# Altium_STM32_Schematic_SchDoc.net
KiCad netlist of a schematic drawn in Altium Designer
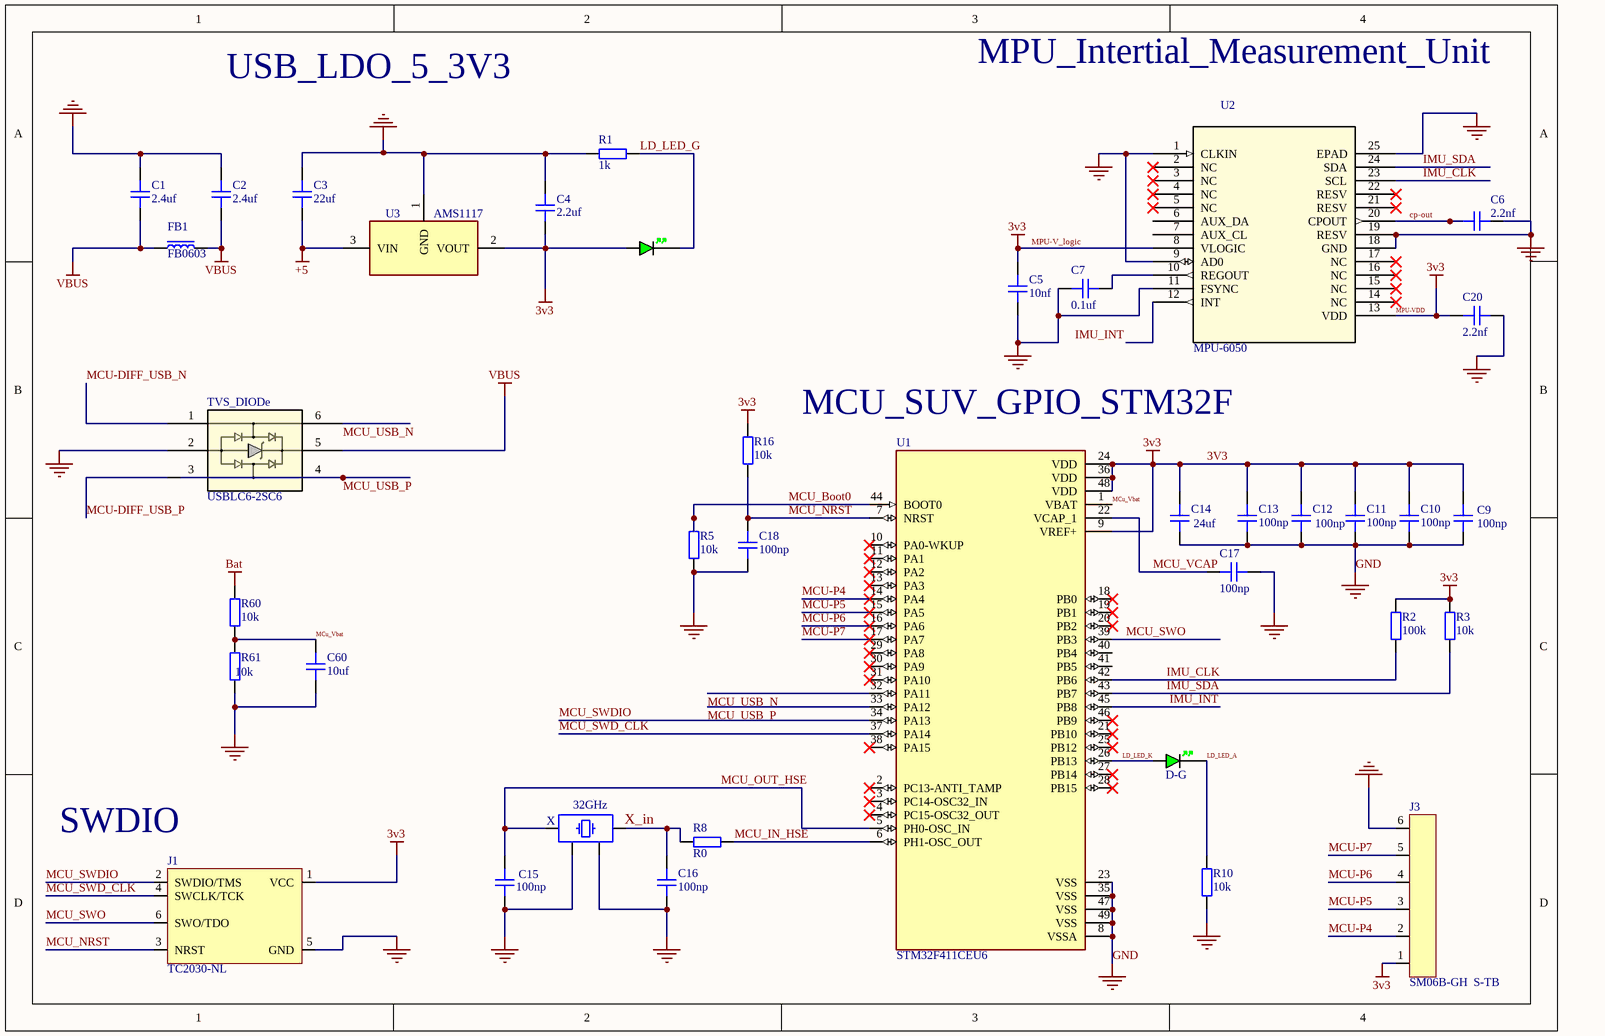
[diagram p0: Altium_STM32_Schematic_SchDoc.SchDoc]

(export (version "E")
  (design (tool "Eeschema 10.0.6"))
  (components
    (comp (ref "C1")
      (value "2.4uf")
      (footprint "CAP_0603")
      (description "Capacitor SMD 0603")
      (libsource (lib "Schematic-Lib-PhilsLab") (part "CAP_0603"))
    )
    (comp (ref "C2")
      (value "2.4uf")
      (footprint "CAP_0603")
      (description "Capacitor SMD 0603")
      (libsource (lib "Schematic-Lib-PhilsLab") (part "CAP_0603"))
    )
    (comp (ref "C3")
      (value "22uf")
      (footprint "CAP_0805")
      (description "Capacitor SMD 0805")
      (libsource (lib "Schematic-Lib-PhilsLab") (part "CAP_0805"))
    )
    (comp (ref "C4")
      (value "2.2uf")
      (footprint "CAP_0805")
      (description "Capacitor SMD 0805")
      (libsource (lib "Schematic-Lib-PhilsLab") (part "CAP_0805"))
    )
    (comp (ref "C5")
      (value "10nf")
      (footprint "CAP_0603")
      (description "Capacitor SMD 0603")
      (libsource (lib "Schematic-Lib-PhilsLab") (part "CAP_0603"))
    )
    (comp (ref "C6")
      (value "2.2nf")
      (footprint "CAP_0603")
      (description "Capacitor SMD 0603")
      (libsource (lib "Schematic-Lib-PhilsLab") (part "CAP_0603"))
    )
    (comp (ref "C7")
      (value "0.1uf")
      (footprint "CAP_0603")
      (description "Capacitor SMD 0603")
      (libsource (lib "Schematic-Lib-PhilsLab") (part "CAP_0603"))
    )
    (comp (ref "C9")
      (value "100np")
      (footprint "CAP_0402")
      (description "Capacitor SMD 0402")
      (libsource (lib "Schematic-Lib-PhilsLab") (part "CAP_0402"))
    )
    (comp (ref "C10")
      (value "100np")
      (footprint "CAP_0402")
      (description "Capacitor SMD 0402")
      (libsource (lib "Schematic-Lib-PhilsLab") (part "CAP_0402"))
    )
    (comp (ref "C11")
      (value "100np")
      (footprint "CAP_0402")
      (description "Capacitor SMD 0402")
      (libsource (lib "Schematic-Lib-PhilsLab") (part "CAP_0402"))
    )
    (comp (ref "C12")
      (value "100np")
      (footprint "CAP_0402")
      (description "Capacitor SMD 0402")
      (libsource (lib "Schematic-Lib-PhilsLab") (part "CAP_0402"))
    )
    (comp (ref "C13")
      (value "100np")
      (footprint "CAP_0402")
      (description "Capacitor SMD 0402")
      (libsource (lib "Schematic-Lib-PhilsLab") (part "CAP_0402"))
    )
    (comp (ref "C14")
      (value "24uf")
      (footprint "CAP_0603")
      (description "Capacitor SMD 0603")
      (libsource (lib "Schematic-Lib-PhilsLab") (part "CAP_0603"))
    )
    (comp (ref "C15")
      (value "100np")
      (footprint "CAP_0402")
      (description "Capacitor SMD 0402")
      (libsource (lib "Schematic-Lib-PhilsLab") (part "CAP_0402"))
    )
    (comp (ref "C16")
      (value "100np")
      (footprint "CAP_0402")
      (description "Capacitor SMD 0402")
      (libsource (lib "Schematic-Lib-PhilsLab") (part "CAP_0402"))
    )
    (comp (ref "C17")
      (value "100np")
      (footprint "CAP_0402")
      (description "Capacitor SMD 0402")
      (libsource (lib "Schematic-Lib-PhilsLab") (part "CAP_0402"))
    )
    (comp (ref "C18")
      (value "100np")
      (footprint "CAP_0402")
      (description "Capacitor SMD 0402")
      (libsource (lib "Schematic-Lib-PhilsLab") (part "CAP_0402"))
    )
    (comp (ref "C20")
      (value "2.2nf")
      (footprint "CAP_0603")
      (description "Capacitor SMD 0603")
      (libsource (lib "Schematic-Lib-PhilsLab") (part "CAP_0603"))
    )
    (comp (ref "C60")
      (value "10uf")
      (footprint "CAP_0402")
      (description "Capacitor SMD 0402")
      (libsource (lib "Schematic-Lib-PhilsLab") (part "CAP_0402"))
    )
    (comp (ref "D")
      (value "GREEN")
      (footprint "LED_0402_GREEN")
      (description "LED 0402 GREEN SMD")
      (libsource (lib "Schematic-Lib-PhilsLab") (part "LED_0402_GREEN"))
    )
    (comp (ref "D-G")
      (value "GREEN")
      (footprint "LED_0402_GREEN")
      (description "LED 0402 GREEN SMD")
      (libsource (lib "Schematic-Lib-PhilsLab") (part "LED_0402_GREEN"))
    )
    (comp (ref "FB1")
      (value "FB0603")
      (footprint "FB_0603")
      (description "Ferrite Bead SMD 0603")
      (libsource (lib "Schematic-Lib-PhilsLab") (part "FB_0603"))
    )
    (comp (ref "J1")
      (value "TC2030-NL")
      (footprint "TC2030-NL-FP")
      (description "Tag-Connect No-Solder SWD Debug Connector (No Legs) DO NOT PLACE")
      (fields
        (field (name "MANUFACTURER") "Tag-Connect")
        (field (name "MANUFACTURER PART NUMBER") "TC2030-NL-FP")
      )
      (libsource (lib "Schematic-Lib-PhilsLab") (part "TC2030-NL"))
    )
    (comp (ref "J3")
      (value "SM06B-GH  S-TB")
      (footprint "SM06B-GHS-TB")
      (description "Header Connector 6 Position 1.25MM Pitch SMD Horizontal JST GH")
      (fields (field (name "MANUFACTURER") "JST") (field (name "MANUFACTURER PART NUMBER") "SM06B-GHS-TB"))
      (libsource (lib "Schematic-Lib-PhilsLab") (part "SM06B-GHS-TB"))
    )
    (comp (ref "R1")
      (value "1k")
      (footprint "RES_0402")
      (description "Resistor SMD 0402")
      (libsource (lib "Schematic-Lib-PhilsLab") (part "RES_0402"))
    )
    (comp (ref "R2")
      (value "100k")
      (footprint "RES_0402")
      (description "Resistor SMD 0402")
      (libsource (lib "Schematic-Lib-PhilsLab") (part "RES_0402"))
    )
    (comp (ref "R3")
      (value "10k")
      (footprint "RES_0402")
      (description "Resistor SMD 0402")
      (libsource (lib "Schematic-Lib-PhilsLab") (part "RES_0402"))
    )
    (comp (ref "R5")
      (value "10k")
      (footprint "RES_0402")
      (description "Resistor SMD 0402")
      (libsource (lib "Schematic-Lib-PhilsLab (1)") (part "RES_0402"))
    )
    (comp (ref "R8")
      (value "R0")
      (footprint "RES_0402")
      (description "Resistor SMD 0402")
      (libsource (lib "Schematic-Lib-PhilsLab (1)") (part "RES_0402"))
    )
    (comp (ref "R10")
      (value "10k")
      (footprint "RES_0402")
      (description "Resistor SMD 0402")
      (libsource (lib "Schematic-Lib-PhilsLab") (part "RES_0402"))
    )
    (comp (ref "R16")
      (value "10k")
      (footprint "RES_0402")
      (description "Resistor SMD 0402")
      (libsource (lib "Schematic-Lib-PhilsLab (1)") (part "RES_0402"))
    )
    (comp (ref "R60")
      (value "10k")
      (footprint "RES_0402")
      (description "Resistor SMD 0402")
      (libsource (lib "Schematic-Lib-PhilsLab") (part "RES_0402"))
    )
    (comp (ref "R61")
      (value "10k")
      (footprint "RES_0402")
      (description "Resistor SMD 0402")
      (libsource (lib "Schematic-Lib-PhilsLab") (part "RES_0402"))
    )
    (comp (ref "TVS_DIODe")
      (value "USBLC6-2SC6")
      (footprint "SOT23-6L_STM")
      (description "ESD Protection for USB 2.0 High Speed")
      (fields (field (name "COPYRIGHT") "Copyright (C) 2025 Ultra Librarian. All rights reserved."))
      (libsource (lib "USBLC6-2SC6") (part "USBLC6-2SC6"))
    )
    (comp (ref "U1")
      (value "STM32F411CEU6")
      (footprint "QFN50P700X700X60-49N")
      (libsource (lib "STM32F411CEU6 (1)") (part "STM32F411CEU6"))
    )
    (comp (ref "U2")
      (value "MPU-6050")
      (footprint "QFN24_4X4X0P9-0P5_TDK")
      (description "Description")
      (fields (field (name "COPYRIGHT") "Copyright (C) 2025 Ultra Librarian. All rights reserved."))
      (libsource (lib "MPU-6050") (part "MPU-6050"))
    )
    (comp (ref "U3")
      (value "AMS1117")
      (footprint "AMS1117")
      (description "IC REG LINEAR 1A SOT-89-3L")
      (libsource (lib "Voltage Regulators") (part "AMS1117"))
    )
    (comp (ref "X")
      (value "32GHz")
      (footprint "XTAL_2016")
      (description "Crystal SMD 4-Pin 2.0x1.6mm")
      (libsource (lib "Schematic-Lib-PhilsLab (1)") (part "XTAL_2016"))
    )
  )
  (nets
    (net (code "1") (name "+5") (class "Default")
      (node (ref "C3") (pin "1") (pinfunction "1_1") (pintype "passive"))
      (node (ref "U3") (pin "3") (pinfunction "VIN_3") (pintype "passive"))
    )
    (net (code "2") (name "/IMU_CLK") (class "Default")
      (node (ref "R2") (pin "1") (pinfunction "1_1") (pintype "passive"))
      (node (ref "U1") (pin "42") (pinfunction "PB6_42") (pintype "bidirectional"))
      (node (ref "U2") (pin "23") (pinfunction "SCL_23") (pintype "passive"))
    )
    (net (code "3") (name "/IMU_INT") (class "Default")
      (node (ref "U1") (pin "45") (pinfunction "PB8_45") (pintype "bidirectional"))
      (node (ref "U2") (pin "12") (pinfunction "INT_12") (pintype "output"))
    )
    (net (code "4") (name "/IMU_SDA") (class "Default")
      (node (ref "R3") (pin "1") (pinfunction "1_1") (pintype "passive"))
      (node (ref "U1") (pin "43") (pinfunction "PB7_43") (pintype "bidirectional"))
      (node (ref "U2") (pin "24") (pinfunction "SDA_24") (pintype "passive"))
    )
    (net (code "5") (name "/LD_LED_A") (class "Default")
      (node (ref "D-G") (pin "K") (pinfunction "K_K") (pintype "passive"))
      (node (ref "R10") (pin "1") (pinfunction "1_1") (pintype "passive"))
    )
    (net (code "6") (name "/LD_LED_G") (class "Default")
      (node (ref "D") (pin "K") (pinfunction "K_K") (pintype "passive"))
      (node (ref "R1") (pin "2") (pinfunction "2_2") (pintype "passive"))
    )
    (net (code "7") (name "/LD_LED_K") (class "Default")
      (node (ref "D-G") (pin "A") (pinfunction "A_A") (pintype "passive"))
      (node (ref "U1") (pin "26") (pinfunction "PB13_26") (pintype "bidirectional"))
    )
    (net (code "8") (name "/MCU-DIFF_USB_N") (class "Default")
      (node (ref "TVS_DIODe") (pin "1") (pinfunction "1_1") (pintype "passive"))
    )
    (net (code "9") (name "/MCU-DIFF_USB_P") (class "Default")
      (node (ref "TVS_DIODe") (pin "3") (pinfunction "3_3") (pintype "passive"))
    )
    (net (code "10") (name "/MCU-P4") (class "Default")
      (node (ref "J3") (pin "2") (pinfunction "2_2") (pintype "passive"))
      (node (ref "U1") (pin "14") (pinfunction "PA4_14") (pintype "bidirectional"))
    )
    (net (code "11") (name "/MCU-P5") (class "Default")
      (node (ref "J3") (pin "3") (pinfunction "3_3") (pintype "passive"))
      (node (ref "U1") (pin "15") (pinfunction "PA5_15") (pintype "bidirectional"))
    )
    (net (code "12") (name "/MCU-P6") (class "Default")
      (node (ref "J3") (pin "4") (pinfunction "4_4") (pintype "passive"))
      (node (ref "U1") (pin "16") (pinfunction "PA6_16") (pintype "bidirectional"))
    )
    (net (code "13") (name "/MCU-P7") (class "Default")
      (node (ref "J3") (pin "5") (pinfunction "5_5") (pintype "passive"))
      (node (ref "U1") (pin "17") (pinfunction "PA7_17") (pintype "bidirectional"))
    )
    (net (code "14") (name "/MCU_Boot0") (class "Default")
      (node (ref "R5") (pin "2") (pinfunction "2_2") (pintype "passive"))
      (node (ref "U1") (pin "44") (pinfunction "BOOT0_44") (pintype "input"))
    )
    (net (code "15") (name "/MCU_IN_HSE") (class "Default")
      (node (ref "R8") (pin "2") (pinfunction "2_2") (pintype "passive"))
      (node (ref "U1") (pin "6") (pinfunction "PH1-OSC_OUT_6") (pintype "bidirectional"))
    )
    (net (code "16") (name "/MCU_NRST") (class "Default")
      (node (ref "C18") (pin "1") (pinfunction "1_1") (pintype "passive"))
      (node (ref "J1") (pin "3") (pinfunction "NRST_3") (pintype "passive"))
      (node (ref "R16") (pin "1") (pinfunction "1_1") (pintype "passive"))
      (node (ref "U1") (pin "7") (pinfunction "NRST_7") (pintype "bidirectional"))
    )
    (net (code "17") (name "/MCU_OUT_HSE") (class "Default")
      (node (ref "C15") (pin "2") (pinfunction "2_2") (pintype "passive"))
      (node (ref "U1") (pin "5") (pinfunction "PH0-OSC_IN_5") (pintype "bidirectional"))
      (node (ref "X") (pin "1") (pinfunction "1_1") (pintype "passive"))
    )
    (net (code "18") (name "/MCU_SWDIO") (class "Default")
      (node (ref "J1") (pin "2") (pinfunction "SWDIO/TMS_2") (pintype "passive"))
      (node (ref "U1") (pin "34") (pinfunction "PA13_34") (pintype "bidirectional"))
    )
    (net (code "19") (name "/MCU_SWD_CLK") (class "Default")
      (node (ref "J1") (pin "4") (pinfunction "SWCLK/TCK_4") (pintype "passive"))
      (node (ref "U1") (pin "37") (pinfunction "PA14_37") (pintype "bidirectional"))
    )
    (net (code "20") (name "/MCU_SWO") (class "Default")
      (node (ref "J1") (pin "6") (pinfunction "SWO/TDO_6") (pintype "passive"))
      (node (ref "U1") (pin "39") (pinfunction "PB3_39") (pintype "bidirectional"))
    )
    (net (code "21") (name "/MCU_USB_N") (class "Default")
      (node (ref "TVS_DIODe") (pin "6") (pinfunction "6_6") (pintype "passive"))
      (node (ref "U1") (pin "32") (pinfunction "PA11_32") (pintype "bidirectional"))
    )
    (net (code "22") (name "/MCU_USB_P") (class "Default")
      (node (ref "TVS_DIODe") (pin "4") (pinfunction "4_4") (pintype "passive"))
      (node (ref "U1") (pin "33") (pinfunction "PA12_33") (pintype "bidirectional"))
    )
    (net (code "23") (name "/MCU_VCAP") (class "Default")
      (node (ref "C17") (pin "2") (pinfunction "2_2") (pintype "passive"))
      (node (ref "U1") (pin "22") (pinfunction "VCAP_1_22") (pintype "power_in"))
    )
    (net (code "24") (name "/MCu_Vbat") (class "Default")
      (node (ref "C60") (pin "2") (pinfunction "2_2") (pintype "passive"))
      (node (ref "R60") (pin "1") (pinfunction "1_1") (pintype "passive"))
      (node (ref "R61") (pin "1") (pinfunction "1_1") (pintype "passive"))
      (node (ref "U1") (pin "1") (pinfunction "VBAT_1") (pintype "power_in"))
    )
    (net (code "25") (name "/X_in") (class "Default")
      (node (ref "C16") (pin "2") (pinfunction "2_2") (pintype "passive"))
      (node (ref "R8") (pin "1") (pinfunction "1_1") (pintype "passive"))
      (node (ref "X") (pin "3") (pinfunction "3_3") (pintype "passive"))
    )
    (net (code "26") (name "/cp-out") (class "Default")
      (node (ref "C6") (pin "2") (pinfunction "2_2") (pintype "passive"))
      (node (ref "U2") (pin "20") (pinfunction "CPOUT_20") (pintype "output"))
    )
    (net (code "27") (name "3v3") (class "Default")
      (node (ref "C10") (pin "2") (pinfunction "2_2") (pintype "passive"))
      (node (ref "C11") (pin "2") (pinfunction "2_2") (pintype "passive"))
      (node (ref "C12") (pin "2") (pinfunction "2_2") (pintype "passive"))
      (node (ref "C13") (pin "2") (pinfunction "2_2") (pintype "passive"))
      (node (ref "C14") (pin "2") (pinfunction "2_2") (pintype "passive"))
      (node (ref "C20") (pin "2") (pinfunction "2_2") (pintype "passive"))
      (node (ref "C4") (pin "2") (pinfunction "2_2") (pintype "passive"))
      (node (ref "C5") (pin "2") (pinfunction "2_2") (pintype "passive"))
      (node (ref "C9") (pin "2") (pinfunction "2_2") (pintype "passive"))
      (node (ref "D") (pin "A") (pinfunction "A_A") (pintype "passive"))
      (node (ref "J1") (pin "1") (pinfunction "VCC_1") (pintype "passive"))
      (node (ref "J3") (pin "1") (pinfunction "1_1") (pintype "passive"))
      (node (ref "R16") (pin "2") (pinfunction "2_2") (pintype "passive"))
      (node (ref "R2") (pin "2") (pinfunction "2_2") (pintype "passive"))
      (node (ref "R3") (pin "2") (pinfunction "2_2") (pintype "passive"))
      (node (ref "U1") (pin "24") (pinfunction "VDD_24") (pintype "power_in"))
      (node (ref "U1") (pin "36") (pinfunction "VDD_36") (pintype "power_in"))
      (node (ref "U1") (pin "48") (pinfunction "VDD_48") (pintype "power_in"))
      (node (ref "U1") (pin "9") (pinfunction "VREF+_9") (pintype "power_in"))
      (node (ref "U2") (pin "13") (pinfunction "VDD_13") (pintype "power_in"))
      (node (ref "U2") (pin "8") (pinfunction "VLOGIC_8") (pintype "power_in"))
      (node (ref "U3") (pin "2") (pinfunction "VOUT_2") (pintype "passive"))
    )
    (net (code "28") (name "Bat") (class "Default")
      (node (ref "R60") (pin "2") (pinfunction "2_2") (pintype "passive"))
    )
    (net (code "29") (name "GND") (class "Default")
      (node (ref "C1") (pin "2") (pinfunction "2_2") (pintype "passive"))
      (node (ref "C10") (pin "1") (pinfunction "1_1") (pintype "passive"))
      (node (ref "C11") (pin "1") (pinfunction "1_1") (pintype "passive"))
      (node (ref "C12") (pin "1") (pinfunction "1_1") (pintype "passive"))
      (node (ref "C13") (pin "1") (pinfunction "1_1") (pintype "passive"))
      (node (ref "C14") (pin "1") (pinfunction "1_1") (pintype "passive"))
      (node (ref "C15") (pin "1") (pinfunction "1_1") (pintype "passive"))
      (node (ref "C16") (pin "1") (pinfunction "1_1") (pintype "passive"))
      (node (ref "C17") (pin "1") (pinfunction "1_1") (pintype "passive"))
      (node (ref "C18") (pin "2") (pinfunction "2_2") (pintype "passive"))
      (node (ref "C2") (pin "2") (pinfunction "2_2") (pintype "passive"))
      (node (ref "C20") (pin "1") (pinfunction "1_1") (pintype "passive"))
      (node (ref "C3") (pin "2") (pinfunction "2_2") (pintype "passive"))
      (node (ref "C4") (pin "1") (pinfunction "1_1") (pintype "passive"))
      (node (ref "C5") (pin "1") (pinfunction "1_1") (pintype "passive"))
      (node (ref "C6") (pin "1") (pinfunction "1_1") (pintype "passive"))
      (node (ref "C60") (pin "1") (pinfunction "1_1") (pintype "passive"))
      (node (ref "C7") (pin "1") (pinfunction "1_1") (pintype "passive"))
      (node (ref "C9") (pin "1") (pinfunction "1_1") (pintype "passive"))
      (node (ref "J1") (pin "5") (pinfunction "GND_5") (pintype "passive"))
      (node (ref "J3") (pin "6") (pinfunction "6_6") (pintype "passive"))
      (node (ref "R1") (pin "1") (pinfunction "1_1") (pintype "passive"))
      (node (ref "R10") (pin "2") (pinfunction "2_2") (pintype "passive"))
      (node (ref "R5") (pin "1") (pinfunction "1_1") (pintype "passive"))
      (node (ref "R61") (pin "2") (pinfunction "2_2") (pintype "passive"))
      (node (ref "TVS_DIODe") (pin "2") (pinfunction "2_2") (pintype "passive"))
      (node (ref "U1") (pin "23") (pinfunction "VSS_23") (pintype "power_in"))
      (node (ref "U1") (pin "35") (pinfunction "VSS_35") (pintype "power_in"))
      (node (ref "U1") (pin "47") (pinfunction "VSS_47") (pintype "power_in"))
      (node (ref "U1") (pin "49") (pinfunction "VSS_49") (pintype "power_in"))
      (node (ref "U1") (pin "8") (pinfunction "VSSA_8") (pintype "power_in"))
      (node (ref "U2") (pin "1") (pinfunction "CLKIN_1") (pintype "input"))
      (node (ref "U2") (pin "11") (pinfunction "FSYNC_11") (pintype "passive"))
      (node (ref "U2") (pin "18") (pinfunction "GND_18") (pintype "power_in"))
      (node (ref "U2") (pin "19") (pinfunction "RESV_19") (pintype "passive"))
      (node (ref "U2") (pin "25") (pinfunction "EPAD_25") (pintype "passive"))
      (node (ref "U2") (pin "9") (pinfunction "AD0_9") (pintype "bidirectional"))
      (node (ref "U3") (pin "1") (pinfunction "GND_1") (pintype "passive"))
      (node (ref "X") (pin "2") (pinfunction "2_2") (pintype "passive"))
      (node (ref "X") (pin "4") (pinfunction "4_4") (pintype "passive"))
    )
    (net (code "30") (name "Net-(U2-REGOUT)") (class "Default")
      (node (ref "C7") (pin "2") (pinfunction "2_2") (pintype "passive"))
      (node (ref "U2") (pin "10") (pinfunction "REGOUT_10") (pintype "output"))
    )
    (net (code "31") (name "VBUS") (class "Default")
      (node (ref "C1") (pin "1") (pinfunction "1_1") (pintype "passive"))
      (node (ref "C2") (pin "1") (pinfunction "1_1") (pintype "passive"))
      (node (ref "FB1") (pin "1") (pinfunction "1_1") (pintype "passive"))
      (node (ref "FB1") (pin "2") (pinfunction "2_2") (pintype "passive"))
      (node (ref "TVS_DIODe") (pin "5") (pinfunction "5_5") (pintype "passive"))
    )
    (net (code "32") (name "unconnected-(U1-PA0-WKUP-Pad10)") (class "Default")
      (node (ref "U1") (pin "10") (pinfunction "PA0-WKUP_10") (pintype "bidirectional+no_connect"))
    )
    (net (code "33") (name "unconnected-(U1-PA1-Pad11)") (class "Default")
      (node (ref "U1") (pin "11") (pinfunction "PA1_11") (pintype "bidirectional+no_connect"))
    )
    (net (code "34") (name "unconnected-(U1-PA2-Pad12)") (class "Default")
      (node (ref "U1") (pin "12") (pinfunction "PA2_12") (pintype "bidirectional+no_connect"))
    )
    (net (code "35") (name "unconnected-(U1-PA3-Pad13)") (class "Default")
      (node (ref "U1") (pin "13") (pinfunction "PA3_13") (pintype "bidirectional+no_connect"))
    )
    (net (code "36") (name "unconnected-(U1-PA8-Pad29)") (class "Default")
      (node (ref "U1") (pin "29") (pinfunction "PA8_29") (pintype "bidirectional+no_connect"))
    )
    (net (code "37") (name "unconnected-(U1-PA9-Pad30)") (class "Default")
      (node (ref "U1") (pin "30") (pinfunction "PA9_30") (pintype "bidirectional+no_connect"))
    )
    (net (code "38") (name "unconnected-(U1-PA10-Pad31)") (class "Default")
      (node (ref "U1") (pin "31") (pinfunction "PA10_31") (pintype "bidirectional+no_connect"))
    )
    (net (code "39") (name "unconnected-(U1-PA15-Pad38)") (class "Default")
      (node (ref "U1") (pin "38") (pinfunction "PA15_38") (pintype "bidirectional+no_connect"))
    )
    (net (code "40") (name "unconnected-(U1-PB0-Pad18)") (class "Default")
      (node (ref "U1") (pin "18") (pinfunction "PB0_18") (pintype "bidirectional+no_connect"))
    )
    (net (code "41") (name "unconnected-(U1-PB1-Pad19)") (class "Default")
      (node (ref "U1") (pin "19") (pinfunction "PB1_19") (pintype "bidirectional+no_connect"))
    )
    (net (code "42") (name "unconnected-(U1-PB2-Pad20)") (class "Default")
      (node (ref "U1") (pin "20") (pinfunction "PB2_20") (pintype "bidirectional+no_connect"))
    )
    (net (code "43") (name "unconnected-(U1-PB4-Pad40)") (class "Default")
      (node (ref "U1") (pin "40") (pinfunction "PB4_40") (pintype "bidirectional"))
    )
    (net (code "44") (name "unconnected-(U1-PB5-Pad41)") (class "Default")
      (node (ref "U1") (pin "41") (pinfunction "PB5_41") (pintype "bidirectional"))
    )
    (net (code "45") (name "unconnected-(U1-PB9-Pad46)") (class "Default")
      (node (ref "U1") (pin "46") (pinfunction "PB9_46") (pintype "bidirectional+no_connect"))
    )
    (net (code "46") (name "unconnected-(U1-PB10-Pad21)") (class "Default")
      (node (ref "U1") (pin "21") (pinfunction "PB10_21") (pintype "bidirectional+no_connect"))
    )
    (net (code "47") (name "unconnected-(U1-PB12-Pad25)") (class "Default")
      (node (ref "U1") (pin "25") (pinfunction "PB12_25") (pintype "bidirectional+no_connect"))
    )
    (net (code "48") (name "unconnected-(U1-PB14-Pad27)") (class "Default")
      (node (ref "U1") (pin "27") (pinfunction "PB14_27") (pintype "bidirectional+no_connect"))
    )
    (net (code "49") (name "unconnected-(U1-PB15-Pad28)") (class "Default")
      (node (ref "U1") (pin "28") (pinfunction "PB15_28") (pintype "bidirectional+no_connect"))
    )
    (net (code "50") (name "unconnected-(U1-PC13-ANTI_TAMP-Pad2)") (class "Default")
      (node (ref "U1") (pin "2") (pinfunction "PC13-ANTI_TAMP_2") (pintype "bidirectional+no_connect"))
    )
    (net (code "51") (name "unconnected-(U1-PC14-OSC32_IN-Pad3)") (class "Default")
      (node (ref "U1") (pin "3") (pinfunction "PC14-OSC32_IN_3") (pintype "bidirectional+no_connect"))
    )
    (net (code "52") (name "unconnected-(U1-PC15-OSC32_OUT-Pad4)") (class "Default")
      (node (ref "U1") (pin "4") (pinfunction "PC15-OSC32_OUT_4") (pintype "bidirectional+no_connect"))
    )
    (net (code "53") (name "unconnected-(U2-AUX_CL-Pad7)") (class "Default")
      (node (ref "U2") (pin "7") (pinfunction "AUX_CL_7") (pintype "passive"))
    )
    (net (code "54") (name "unconnected-(U2-AUX_DA-Pad6)") (class "Default")
      (node (ref "U2") (pin "6") (pinfunction "AUX_DA_6") (pintype "passive"))
    )
    (net (code "55") (name "unconnected-(U2-NC-Pad2)") (class "Default")
      (node (ref "U2") (pin "2") (pinfunction "NC_2") (pintype "passive+no_connect"))
    )
    (net (code "56") (name "unconnected-(U2-NC-Pad3)") (class "Default")
      (node (ref "U2") (pin "3") (pinfunction "NC_3") (pintype "passive+no_connect"))
    )
    (net (code "57") (name "unconnected-(U2-NC-Pad4)") (class "Default")
      (node (ref "U2") (pin "4") (pinfunction "NC_4") (pintype "passive+no_connect"))
    )
    (net (code "58") (name "unconnected-(U2-NC-Pad5)") (class "Default")
      (node (ref "U2") (pin "5") (pinfunction "NC_5") (pintype "passive+no_connect"))
    )
    (net (code "59") (name "unconnected-(U2-NC-Pad14)") (class "Default")
      (node (ref "U2") (pin "14") (pinfunction "NC_14") (pintype "passive+no_connect"))
    )
    (net (code "60") (name "unconnected-(U2-NC-Pad15)") (class "Default")
      (node (ref "U2") (pin "15") (pinfunction "NC_15") (pintype "passive+no_connect"))
    )
    (net (code "61") (name "unconnected-(U2-NC-Pad16)") (class "Default")
      (node (ref "U2") (pin "16") (pinfunction "NC_16") (pintype "passive+no_connect"))
    )
    (net (code "62") (name "unconnected-(U2-NC-Pad17)") (class "Default")
      (node (ref "U2") (pin "17") (pinfunction "NC_17") (pintype "passive+no_connect"))
    )
    (net (code "63") (name "unconnected-(U2-RESV-Pad21)") (class "Default")
      (node (ref "U2") (pin "21") (pinfunction "RESV_21") (pintype "passive+no_connect"))
    )
    (net (code "64") (name "unconnected-(U2-RESV-Pad22)") (class "Default")
      (node (ref "U2") (pin "22") (pinfunction "RESV_22") (pintype "passive+no_connect"))
    )
  )
)
